# adapter.net
KiCad netlist of a schematic drawn in EAGLE
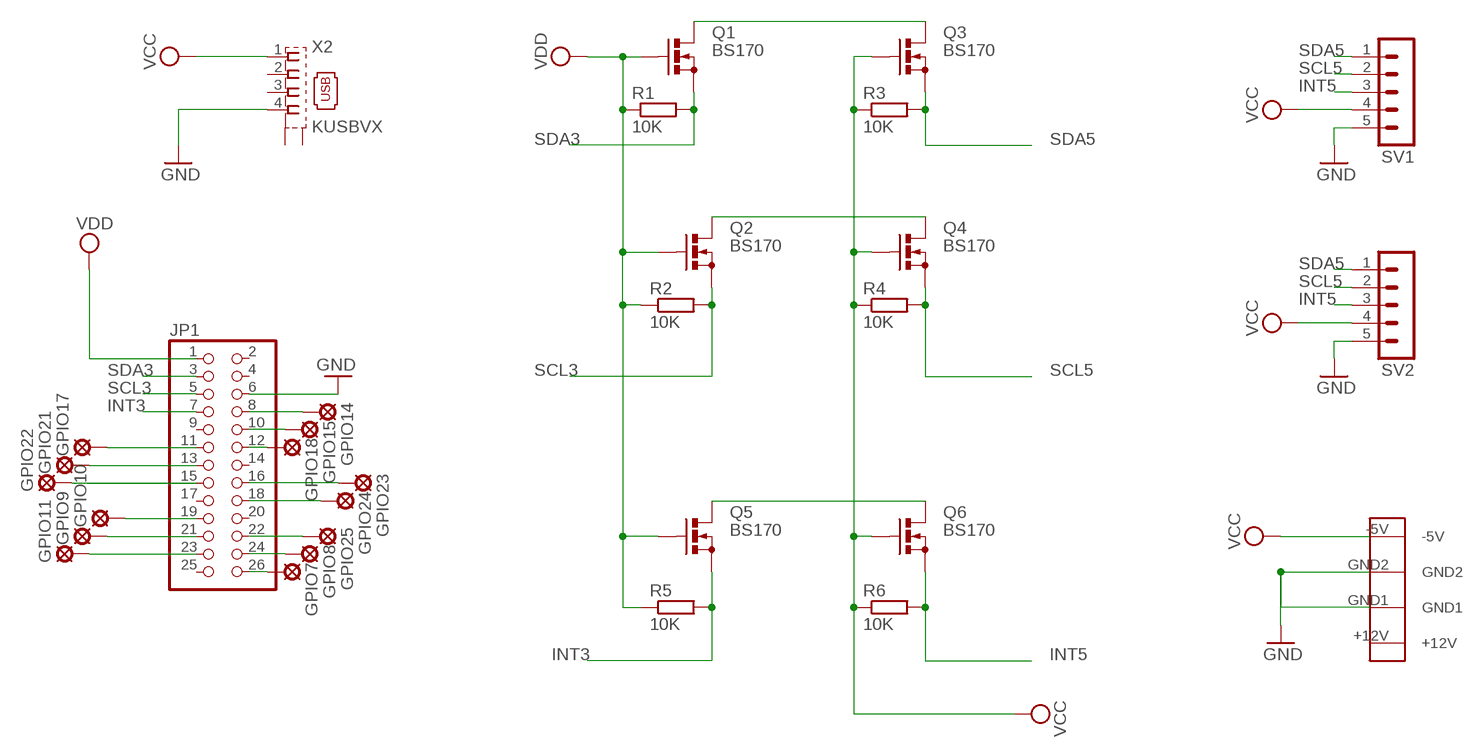
[diagram p0: schematic, sheet 1]

(export (version "E")
  (design (tool "Eeschema 10.0.6"))
  (components
    (comp (ref "GPIO7")
      (value "LSP10")
      (footprint "eagle-import:LSP10")
      (libsource (lib "eagle-import") (part "LSP10"))
    )
    (comp (ref "GPIO8")
      (value "LSP10")
      (footprint "eagle-import:LSP10")
      (libsource (lib "eagle-import") (part "LSP10"))
    )
    (comp (ref "GPIO9")
      (value "LSP10")
      (footprint "eagle-import:LSP10")
      (libsource (lib "eagle-import") (part "LSP10"))
    )
    (comp (ref "GPIO10")
      (value "LSP10")
      (footprint "eagle-import:LSP10")
      (libsource (lib "eagle-import") (part "LSP10"))
    )
    (comp (ref "GPIO11")
      (value "LSP10")
      (footprint "eagle-import:LSP10")
      (libsource (lib "eagle-import") (part "LSP10"))
    )
    (comp (ref "GPIO14")
      (value "LSP10")
      (footprint "eagle-import:LSP10")
      (libsource (lib "eagle-import") (part "LSP10"))
    )
    (comp (ref "GPIO15")
      (value "LSP10")
      (footprint "eagle-import:LSP10")
      (libsource (lib "eagle-import") (part "LSP10"))
    )
    (comp (ref "GPIO17")
      (value "GPIO17")
      (footprint "eagle-import:LSP10")
      (libsource (lib "eagle-import") (part "LSP10"))
    )
    (comp (ref "GPIO18")
      (value "LSP10")
      (footprint "eagle-import:LSP10")
      (libsource (lib "eagle-import") (part "LSP10"))
    )
    (comp (ref "GPIO21")
      (value "LSP10")
      (footprint "eagle-import:LSP10")
      (libsource (lib "eagle-import") (part "LSP10"))
    )
    (comp (ref "GPIO22")
      (value "LSP10")
      (footprint "eagle-import:LSP10")
      (libsource (lib "eagle-import") (part "LSP10"))
    )
    (comp (ref "GPIO23")
      (value "LSP10")
      (footprint "eagle-import:LSP10")
      (libsource (lib "eagle-import") (part "LSP10"))
    )
    (comp (ref "GPIO24")
      (value "LSP10")
      (footprint "eagle-import:LSP10")
      (libsource (lib "eagle-import") (part "LSP10"))
    )
    (comp (ref "GPIO25")
      (value "LSP10")
      (footprint "eagle-import:LSP10")
      (libsource (lib "eagle-import") (part "LSP10"))
    )
    (comp (ref "JP1")
      (value "PINHD-2X13")
      (footprint "eagle-import:2X13")
      (libsource (lib "eagle-import") (part "PINHD-2X13"))
    )
    (comp (ref "Q1")
      (value "BS170")
      (footprint "eagle-import:SOT54E")
      (libsource (lib "eagle-import") (part "BS170"))
    )
    (comp (ref "Q2")
      (value "BS170")
      (footprint "eagle-import:SOT54E")
      (libsource (lib "eagle-import") (part "BS170"))
    )
    (comp (ref "Q3")
      (value "BS170")
      (footprint "eagle-import:SOT54E")
      (libsource (lib "eagle-import") (part "BS170"))
    )
    (comp (ref "Q4")
      (value "BS170")
      (footprint "eagle-import:SOT54E")
      (libsource (lib "eagle-import") (part "BS170"))
    )
    (comp (ref "Q5")
      (value "BS170")
      (footprint "eagle-import:SOT54E")
      (libsource (lib "eagle-import") (part "BS170"))
    )
    (comp (ref "Q6")
      (value "BS170")
      (footprint "eagle-import:SOT54E")
      (libsource (lib "eagle-import") (part "BS170"))
    )
    (comp (ref "R1")
      (value "10K")
      (footprint "eagle-import:0207_2V")
      (libsource (lib "eagle-import") (part "R-EU_0207/2V"))
    )
    (comp (ref "R2")
      (value "10K")
      (footprint "eagle-import:0207_2V")
      (libsource (lib "eagle-import") (part "R-EU_0207/2V"))
    )
    (comp (ref "R3")
      (value "10K")
      (footprint "eagle-import:0207_2V")
      (libsource (lib "eagle-import") (part "R-EU_0207/2V"))
    )
    (comp (ref "R4")
      (value "10K")
      (footprint "eagle-import:0207_2V")
      (libsource (lib "eagle-import") (part "R-EU_0207/2V"))
    )
    (comp (ref "R5")
      (value "10K")
      (footprint "eagle-import:0207_2V")
      (libsource (lib "eagle-import") (part "R-EU_0207/2V"))
    )
    (comp (ref "R6")
      (value "10K")
      (footprint "eagle-import:0207_2V")
      (libsource (lib "eagle-import") (part "R-EU_0207/2V"))
    )
    (comp (ref "SV1")
      (value "MA05-1")
      (footprint "eagle-import:MA05-1")
      (libsource (lib "eagle-import") (part "MA05-1"))
    )
    (comp (ref "SV2")
      (value "MA05-1")
      (footprint "eagle-import:MA05-1")
      (libsource (lib "eagle-import") (part "MA05-1"))
    )
    (comp (ref "U$1")
      (value "PSW_5")
      (footprint "eagle-import:PSW_5")
      (libsource (lib "eagle-import") (part "PSW_5"))
    )
    (comp (ref "X2")
      (value "KUSBVX")
      (footprint "eagle-import:KUSBVX")
      (libsource (lib "eagle-import") (part "KUSBVX"))
    )
  )
  (nets
    (net (code "1") (name "/INT3") (class "Default")
      (node (ref "JP1") (pin "7") (pinfunction "7_7") (pintype "passive"))
      (node (ref "Q5") (pin "S") (pinfunction "S_S") (pintype "passive"))
      (node (ref "R5") (pin "2") (pinfunction "2_2") (pintype "passive"))
    )
    (net (code "2") (name "/INT5") (class "Default")
      (node (ref "Q6") (pin "S") (pinfunction "S_S") (pintype "passive"))
      (node (ref "R6") (pin "2") (pinfunction "2_2") (pintype "passive"))
      (node (ref "SV1") (pin "3") (pinfunction "3_3") (pintype "passive"))
      (node (ref "SV2") (pin "3") (pinfunction "3_3") (pintype "passive"))
    )
    (net (code "3") (name "/SCL3") (class "Default")
      (node (ref "JP1") (pin "5") (pinfunction "5_5") (pintype "passive"))
      (node (ref "Q2") (pin "S") (pinfunction "S_S") (pintype "passive"))
      (node (ref "R2") (pin "2") (pinfunction "2_2") (pintype "passive"))
    )
    (net (code "4") (name "/SCL5") (class "Default")
      (node (ref "Q4") (pin "S") (pinfunction "S_S") (pintype "passive"))
      (node (ref "R4") (pin "2") (pinfunction "2_2") (pintype "passive"))
      (node (ref "SV1") (pin "2") (pinfunction "2_2") (pintype "passive"))
      (node (ref "SV2") (pin "2") (pinfunction "2_2") (pintype "passive"))
    )
    (net (code "5") (name "/SDA3") (class "Default")
      (node (ref "JP1") (pin "3") (pinfunction "3_3") (pintype "passive"))
      (node (ref "Q1") (pin "S") (pinfunction "S_S") (pintype "passive"))
      (node (ref "R1") (pin "2") (pinfunction "2_2") (pintype "passive"))
    )
    (net (code "6") (name "/SDA5") (class "Default")
      (node (ref "Q3") (pin "S") (pinfunction "S_S") (pintype "passive"))
      (node (ref "R3") (pin "2") (pinfunction "2_2") (pintype "passive"))
      (node (ref "SV1") (pin "1") (pinfunction "1_1") (pintype "passive"))
      (node (ref "SV2") (pin "1") (pinfunction "1_1") (pintype "passive"))
    )
    (net (code "7") (name "GND") (class "Default")
      (node (ref "JP1") (pin "6") (pinfunction "6_6") (pintype "passive"))
      (node (ref "SV1") (pin "5") (pinfunction "5_5") (pintype "passive"))
      (node (ref "SV2") (pin "5") (pinfunction "5_5") (pintype "passive"))
      (node (ref "U$1") (pin "GND1") (pinfunction "GND1_GND1") (pintype "bidirectional"))
      (node (ref "U$1") (pin "GND2") (pinfunction "GND2_GND2") (pintype "bidirectional"))
      (node (ref "X2") (pin "4") (pinfunction "4_4") (pintype "passive"))
    )
    (net (code "8") (name "Net-(GPIO7-PadMP)") (class "Default")
      (node (ref "GPIO7") (pin "MP") (pinfunction "MP_MP") (pintype "passive"))
      (node (ref "JP1") (pin "26") (pinfunction "26_26") (pintype "passive"))
    )
    (net (code "9") (name "Net-(GPIO8-PadMP)") (class "Default")
      (node (ref "GPIO8") (pin "MP") (pinfunction "MP_MP") (pintype "passive"))
      (node (ref "JP1") (pin "24") (pinfunction "24_24") (pintype "passive"))
    )
    (net (code "10") (name "Net-(GPIO9-PadMP)") (class "Default")
      (node (ref "GPIO9") (pin "MP") (pinfunction "MP_MP") (pintype "passive"))
      (node (ref "JP1") (pin "21") (pinfunction "21_21") (pintype "passive"))
    )
    (net (code "11") (name "Net-(GPIO10-PadMP)") (class "Default")
      (node (ref "GPIO10") (pin "MP") (pinfunction "MP_MP") (pintype "passive"))
      (node (ref "JP1") (pin "19") (pinfunction "19_19") (pintype "passive"))
    )
    (net (code "12") (name "Net-(GPIO11-PadMP)") (class "Default")
      (node (ref "GPIO11") (pin "MP") (pinfunction "MP_MP") (pintype "passive"))
      (node (ref "JP1") (pin "23") (pinfunction "23_23") (pintype "passive"))
    )
    (net (code "13") (name "Net-(GPIO14-PadMP)") (class "Default")
      (node (ref "GPIO14") (pin "MP") (pinfunction "MP_MP") (pintype "passive"))
      (node (ref "JP1") (pin "8") (pinfunction "8_8") (pintype "passive"))
    )
    (net (code "14") (name "Net-(GPIO15-PadMP)") (class "Default")
      (node (ref "GPIO15") (pin "MP") (pinfunction "MP_MP") (pintype "passive"))
      (node (ref "JP1") (pin "10") (pinfunction "10_10") (pintype "passive"))
    )
    (net (code "15") (name "Net-(GPIO17-PadMP)") (class "Default")
      (node (ref "GPIO17") (pin "MP") (pinfunction "MP_MP") (pintype "passive"))
      (node (ref "JP1") (pin "11") (pinfunction "11_11") (pintype "passive"))
    )
    (net (code "16") (name "Net-(GPIO18-PadMP)") (class "Default")
      (node (ref "GPIO18") (pin "MP") (pinfunction "MP_MP") (pintype "passive"))
      (node (ref "JP1") (pin "12") (pinfunction "12_12") (pintype "passive"))
    )
    (net (code "17") (name "Net-(GPIO21-PadMP)") (class "Default")
      (node (ref "GPIO21") (pin "MP") (pinfunction "MP_MP") (pintype "passive"))
      (node (ref "JP1") (pin "13") (pinfunction "13_13") (pintype "passive"))
    )
    (net (code "18") (name "Net-(GPIO22-PadMP)") (class "Default")
      (node (ref "GPIO22") (pin "MP") (pinfunction "MP_MP") (pintype "passive"))
      (node (ref "JP1") (pin "15") (pinfunction "15_15") (pintype "passive"))
    )
    (net (code "19") (name "Net-(GPIO23-PadMP)") (class "Default")
      (node (ref "GPIO23") (pin "MP") (pinfunction "MP_MP") (pintype "passive"))
      (node (ref "JP1") (pin "16") (pinfunction "16_16") (pintype "passive"))
    )
    (net (code "20") (name "Net-(GPIO24-PadMP)") (class "Default")
      (node (ref "GPIO24") (pin "MP") (pinfunction "MP_MP") (pintype "passive"))
      (node (ref "JP1") (pin "18") (pinfunction "18_18") (pintype "passive"))
    )
    (net (code "21") (name "Net-(GPIO25-PadMP)") (class "Default")
      (node (ref "GPIO25") (pin "MP") (pinfunction "MP_MP") (pintype "passive"))
      (node (ref "JP1") (pin "22") (pinfunction "22_22") (pintype "passive"))
    )
    (net (code "22") (name "Net-(Q1-PadD)") (class "Default")
      (node (ref "Q1") (pin "D") (pinfunction "D_D") (pintype "passive"))
      (node (ref "Q3") (pin "D") (pinfunction "D_D") (pintype "passive"))
    )
    (net (code "23") (name "Net-(Q2-PadD)") (class "Default")
      (node (ref "Q2") (pin "D") (pinfunction "D_D") (pintype "passive"))
      (node (ref "Q4") (pin "D") (pinfunction "D_D") (pintype "passive"))
    )
    (net (code "24") (name "Net-(Q5-PadD)") (class "Default")
      (node (ref "Q5") (pin "D") (pinfunction "D_D") (pintype "passive"))
      (node (ref "Q6") (pin "D") (pinfunction "D_D") (pintype "passive"))
    )
    (net (code "25") (name "VCC") (class "Default")
      (node (ref "Q3") (pin "G") (pinfunction "G_G") (pintype "passive"))
      (node (ref "Q4") (pin "G") (pinfunction "G_G") (pintype "passive"))
      (node (ref "Q6") (pin "G") (pinfunction "G_G") (pintype "passive"))
      (node (ref "R3") (pin "1") (pinfunction "1_1") (pintype "passive"))
      (node (ref "R4") (pin "1") (pinfunction "1_1") (pintype "passive"))
      (node (ref "R6") (pin "1") (pinfunction "1_1") (pintype "passive"))
      (node (ref "SV1") (pin "4") (pinfunction "4_4") (pintype "passive"))
      (node (ref "SV2") (pin "4") (pinfunction "4_4") (pintype "passive"))
      (node (ref "U$1") (pin "-5V") (pinfunction "-5V_-5V") (pintype "bidirectional"))
      (node (ref "X2") (pin "1") (pinfunction "1_1") (pintype "passive"))
    )
    (net (code "26") (name "VDD") (class "Default")
      (node (ref "JP1") (pin "1") (pinfunction "1_1") (pintype "passive"))
      (node (ref "Q1") (pin "G") (pinfunction "G_G") (pintype "passive"))
      (node (ref "Q2") (pin "G") (pinfunction "G_G") (pintype "passive"))
      (node (ref "Q5") (pin "G") (pinfunction "G_G") (pintype "passive"))
      (node (ref "R1") (pin "1") (pinfunction "1_1") (pintype "passive"))
      (node (ref "R2") (pin "1") (pinfunction "1_1") (pintype "passive"))
      (node (ref "R5") (pin "1") (pinfunction "1_1") (pintype "passive"))
    )
    (net (code "27") (name "unconnected-(JP1-Pad2)") (class "Default")
      (node (ref "JP1") (pin "2") (pinfunction "2_2") (pintype "passive"))
    )
    (net (code "28") (name "unconnected-(JP1-Pad4)") (class "Default")
      (node (ref "JP1") (pin "4") (pinfunction "4_4") (pintype "passive"))
    )
    (net (code "29") (name "unconnected-(JP1-Pad9)") (class "Default")
      (node (ref "JP1") (pin "9") (pinfunction "9_9") (pintype "passive"))
    )
    (net (code "30") (name "unconnected-(JP1-Pad14)") (class "Default")
      (node (ref "JP1") (pin "14") (pinfunction "14_14") (pintype "passive"))
    )
    (net (code "31") (name "unconnected-(JP1-Pad17)") (class "Default")
      (node (ref "JP1") (pin "17") (pinfunction "17_17") (pintype "passive"))
    )
    (net (code "32") (name "unconnected-(JP1-Pad20)") (class "Default")
      (node (ref "JP1") (pin "20") (pinfunction "20_20") (pintype "passive"))
    )
    (net (code "33") (name "unconnected-(JP1-Pad25)") (class "Default")
      (node (ref "JP1") (pin "25") (pinfunction "25_25") (pintype "passive"))
    )
    (net (code "34") (name "unconnected-(U$1-Pad+12V)") (class "Default")
      (node (ref "U$1") (pin "+12V") (pinfunction "+12V_+12V") (pintype "bidirectional"))
    )
    (net (code "35") (name "unconnected-(X2-Pad2)") (class "Default")
      (node (ref "X2") (pin "2") (pinfunction "2_2") (pintype "passive"))
    )
    (net (code "36") (name "unconnected-(X2-Pad3)") (class "Default")
      (node (ref "X2") (pin "3") (pinfunction "3_3") (pintype "passive"))
    )
    (net (code "37") (name "unconnected-(X2-S1-PadM1)") (class "Default")
      (node (ref "X2") (pin "M1") (pinfunction "S1_M1") (pintype "passive"))
    )
    (net (code "38") (name "unconnected-(X2-S2-PadM2)") (class "Default")
      (node (ref "X2") (pin "M2") (pinfunction "S2_M2") (pintype "passive"))
    )
  )
)
